# Light_bar.net
KiCad netlist of a schematic drawn in EAGLE
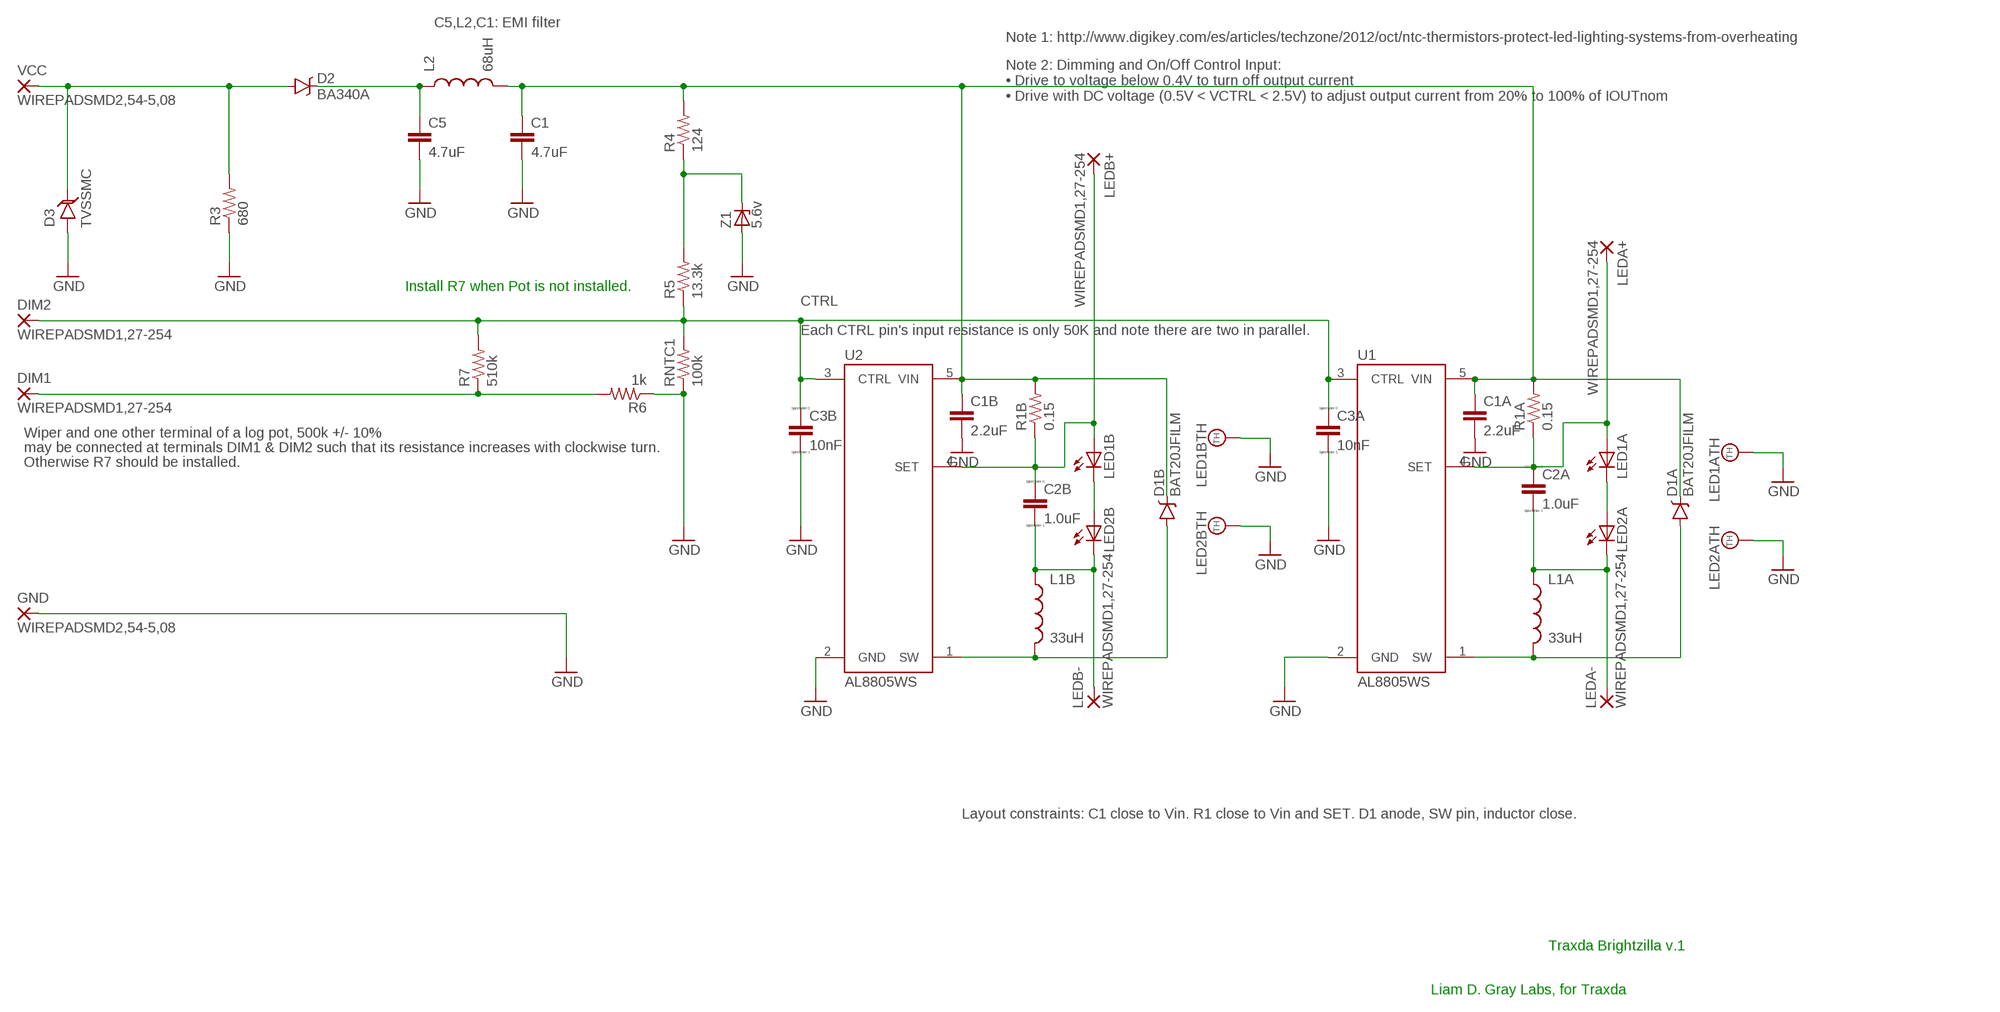
[diagram p0: schematic, sheet 1]

(export (version "E")
  (design (tool "Eeschema 10.0.6"))
  (components
    (comp (ref "C1")
      (value "4.7uF")
      (footprint "eagle-import:1210")
      (libsource (lib "eagle-import") (part "SparkFun-Passives_CAP1210"))
    )
    (comp (ref "C1A")
      (value "2.2uF")
      (footprint "eagle-import:0805")
      (libsource (lib "eagle-import") (part "2.2UF-25V-+80/-20(0805)"))
    )
    (comp (ref "C1B")
      (value "2.2uF")
      (footprint "eagle-import:0805")
      (libsource (lib "eagle-import") (part "2.2UF-25V-+80/-20(0805)"))
    )
    (comp (ref "C2A")
      (value "1.0uF")
      (footprint "eagle-import:0805")
      (libsource (lib "eagle-import") (part "1.0UF-25V-+80/-20(0805)"))
    )
    (comp (ref "C2B")
      (value "1.0uF")
      (footprint "eagle-import:0805")
      (libsource (lib "eagle-import") (part "1.0UF-25V-+80/-20(0805)"))
    )
    (comp (ref "C3A")
      (value "10nF")
      (footprint "eagle-import:0603-CAP")
      (libsource (lib "eagle-import") (part "10NF/10000PF-50V-10%(0603)"))
    )
    (comp (ref "C3B")
      (value "10nF")
      (footprint "eagle-import:0603-CAP")
      (libsource (lib "eagle-import") (part "CAP0603-CAP"))
    )
    (comp (ref "C5")
      (value "4.7uF")
      (footprint "eagle-import:1210")
      (libsource (lib "eagle-import") (part "SparkFun-Passives_CAP1210"))
    )
    (comp (ref "D1A")
      (value "BAT20JFILM")
      (footprint "eagle-import:SOD-323")
      (libsource (lib "eagle-import") (part "BAT20JFILM"))
    )
    (comp (ref "D1B")
      (value "BAT20JFILM")
      (footprint "eagle-import:SOD-323")
      (libsource (lib "eagle-import") (part "BAT20JFILM"))
    )
    (comp (ref "D2")
      (value "BA340A")
      (footprint "eagle-import:SMA-DIODE")
      (libsource (lib "eagle-import") (part "B340A"))
    )
    (comp (ref "D3")
      (value "TVSSMC")
      (footprint "eagle-import:SMC")
      (libsource (lib "eagle-import") (part "TVSSMC"))
    )
    (comp (ref "DIM1")
      (value "WIREPADSMD1,27-254")
      (footprint "eagle-import:SMD1,27-2,54")
      (libsource (lib "eagle-import") (part "WIREPADSMD1,27-254"))
    )
    (comp (ref "DIM2")
      (value "WIREPADSMD1,27-254")
      (footprint "eagle-import:SMD1,27-2,54")
      (libsource (lib "eagle-import") (part "WIREPADSMD1,27-254"))
    )
    (comp (ref "GND")
      (value "WIREPADSMD2,54-5,08")
      (footprint "eagle-import:SMD2,54-5,08")
      (libsource (lib "eagle-import") (part "WIREPADSMD2,54-5,08"))
    )
    (comp (ref "L1A")
      (value "33uH")
      (footprint "eagle-import:NR6045")
      (libsource (lib "eagle-import") (part "INDUCTORYUDEN_NR6045NR6045T330M"))
    )
    (comp (ref "L1B")
      (value "33uH")
      (footprint "eagle-import:NR6045")
      (libsource (lib "eagle-import") (part "INDUCTORYUDEN_NR6045NR6045T330M"))
    )
    (comp (ref "L2")
      (value "68uH")
      (footprint "eagle-import:SRR1260")
      (libsource (lib "eagle-import") (part "INDUCTORBOURNS_SRR1260"))
    )
    (comp (ref "LED1A")
      (value "LUXEON_REBEL")
      (footprint "eagle-import:LUXEON_REBEL_32MIL12MIL")
      (libsource (lib "eagle-import") (part "LUXEON_REBEL"))
    )
    (comp (ref "LED1B")
      (value "LUXEON_REBEL")
      (footprint "eagle-import:LUXEON_REBEL_32MIL12MIL")
      (libsource (lib "eagle-import") (part "LUXEON_REBEL"))
    )
    (comp (ref "LED2A")
      (value "LUXEON_REBEL")
      (footprint "eagle-import:LUXEON_REBEL_32MIL12MIL")
      (libsource (lib "eagle-import") (part "LUXEON_REBEL"))
    )
    (comp (ref "LED2B")
      (value "LUXEON_REBEL")
      (footprint "eagle-import:LUXEON_REBEL_32MIL12MIL")
      (libsource (lib "eagle-import") (part "LUXEON_REBEL"))
    )
    (comp (ref "LEDA+")
      (value "WIREPADSMD1,27-254")
      (footprint "eagle-import:SMD1,27-2,54")
      (libsource (lib "eagle-import") (part "WIREPADSMD1,27-254"))
    )
    (comp (ref "LEDA-")
      (value "WIREPADSMD1,27-254")
      (footprint "eagle-import:SMD1,27-2,54")
      (libsource (lib "eagle-import") (part "WIREPADSMD1,27-254"))
    )
    (comp (ref "LEDB+")
      (value "WIREPADSMD1,27-254")
      (footprint "eagle-import:SMD1,27-2,54")
      (libsource (lib "eagle-import") (part "WIREPADSMD1,27-254"))
    )
    (comp (ref "LEDB-")
      (value "WIREPADSMD1,27-254")
      (footprint "eagle-import:SMD1,27-2,54")
      (libsource (lib "eagle-import") (part "WIREPADSMD1,27-254"))
    )
    (comp (ref "R1A")
      (value "0.15")
      (footprint "eagle-import:0805")
      (libsource (lib "eagle-import") (part "0.3OHM-1/8W-1%(0805)"))
    )
    (comp (ref "R1B")
      (value "0.15")
      (footprint "eagle-import:0805")
      (libsource (lib "eagle-import") (part "0.3OHM-1/8W-1%(0805)"))
    )
    (comp (ref "R3")
      (value "680")
      (footprint "eagle-import:R2512")
      (libsource (lib "eagle-import") (part "RESISTOR2512"))
    )
    (comp (ref "R4")
      (value "124")
      (footprint "eagle-import:R1210")
      (libsource (lib "eagle-import") (part "R-US_R1210"))
    )
    (comp (ref "R5")
      (value "13.3k")
      (footprint "eagle-import:R0805")
      (libsource (lib "eagle-import") (part "R-US_R0805"))
    )
    (comp (ref "R6")
      (value "1k")
      (footprint "eagle-import:0603-RES")
      (libsource (lib "eagle-import") (part "RESISTOR0603-RES"))
    )
    (comp (ref "R7")
      (value "510k")
      (footprint "eagle-import:0805")
      (libsource (lib "eagle-import") (part "RESISTOR0805-RES"))
    )
    (comp (ref "RNTC1")
      (value "100k")
      (footprint "eagle-import:0603-RES")
      (libsource (lib "eagle-import") (part "RESISTOR0603-RES"))
    )
    (comp (ref "U1")
      (value "AL8805WS")
      (footprint "eagle-import:SOT23-5")
      (libsource (lib "eagle-import") (part "AL8805"))
    )
    (comp (ref "U2")
      (value "AL8805WS")
      (footprint "eagle-import:SOT23-5")
      (libsource (lib "eagle-import") (part "AL8805"))
    )
    (comp (ref "VCC")
      (value "WIREPADSMD2,54-5,08")
      (footprint "eagle-import:SMD2,54-5,08")
      (libsource (lib "eagle-import") (part "WIREPADSMD2,54-5,08"))
    )
    (comp (ref "Z1")
      (value "5.6v")
      (footprint "eagle-import:SOD80C")
      (libsource (lib "eagle-import") (part "ZENER-DIODESOD80C"))
    )
  )
  (nets
    (net (code "1") (name "/CTRL") (class "Default")
      (node (ref "C3A") (pin "1") (pinfunction "1_1") (pintype "passive"))
      (node (ref "C3B") (pin "1") (pinfunction "1_1") (pintype "passive"))
      (node (ref "DIM2") (pin "1") (pinfunction "P_1") (pintype "passive"))
      (node (ref "R5") (pin "1") (pinfunction "1_1") (pintype "passive"))
      (node (ref "R7") (pin "2") (pinfunction "2_2") (pintype "passive"))
      (node (ref "RNTC1") (pin "2") (pinfunction "2_2") (pintype "passive"))
      (node (ref "U1") (pin "3") (pinfunction "CTRL_3") (pintype "bidirectional"))
      (node (ref "U2") (pin "3") (pinfunction "CTRL_3") (pintype "bidirectional"))
    )
    (net (code "2") (name "GND") (class "Default")
      (node (ref "C1") (pin "2") (pinfunction "2_2") (pintype "passive"))
      (node (ref "C1A") (pin "2") (pinfunction "2_2") (pintype "passive"))
      (node (ref "C1B") (pin "2") (pinfunction "2_2") (pintype "passive"))
      (node (ref "C3A") (pin "2") (pinfunction "2_2") (pintype "passive"))
      (node (ref "C3B") (pin "2") (pinfunction "2_2") (pintype "passive"))
      (node (ref "C5") (pin "2") (pinfunction "2_2") (pintype "passive"))
      (node (ref "D3") (pin "A") (pinfunction "A_A") (pintype "passive"))
      (node (ref "GND") (pin "1") (pinfunction "P_1") (pintype "passive"))
      (node (ref "LED1A") (pin "TH") (pinfunction "TH_TH") (pintype "passive"))
      (node (ref "LED1A") (pin "TH@1") (pinfunction "TH_TH@1") (pintype "passive"))
      (node (ref "LED1A") (pin "TH@2") (pinfunction "TH_TH@2") (pintype "passive"))
      (node (ref "LED1A") (pin "TH@3") (pinfunction "TH_TH@3") (pintype "passive"))
      (node (ref "LED1A") (pin "TH@4") (pinfunction "TH_TH@4") (pintype "passive"))
      (node (ref "LED1B") (pin "TH") (pinfunction "TH_TH") (pintype "passive"))
      (node (ref "LED1B") (pin "TH@1") (pinfunction "TH_TH@1") (pintype "passive"))
      (node (ref "LED1B") (pin "TH@2") (pinfunction "TH_TH@2") (pintype "passive"))
      (node (ref "LED1B") (pin "TH@3") (pinfunction "TH_TH@3") (pintype "passive"))
      (node (ref "LED1B") (pin "TH@4") (pinfunction "TH_TH@4") (pintype "passive"))
      (node (ref "LED2A") (pin "TH") (pinfunction "TH_TH") (pintype "passive"))
      (node (ref "LED2A") (pin "TH@1") (pinfunction "TH_TH@1") (pintype "passive"))
      (node (ref "LED2A") (pin "TH@2") (pinfunction "TH_TH@2") (pintype "passive"))
      (node (ref "LED2A") (pin "TH@3") (pinfunction "TH_TH@3") (pintype "passive"))
      (node (ref "LED2A") (pin "TH@4") (pinfunction "TH_TH@4") (pintype "passive"))
      (node (ref "LED2B") (pin "TH") (pinfunction "TH_TH") (pintype "passive"))
      (node (ref "LED2B") (pin "TH@1") (pinfunction "TH_TH@1") (pintype "passive"))
      (node (ref "LED2B") (pin "TH@2") (pinfunction "TH_TH@2") (pintype "passive"))
      (node (ref "LED2B") (pin "TH@3") (pinfunction "TH_TH@3") (pintype "passive"))
      (node (ref "LED2B") (pin "TH@4") (pinfunction "TH_TH@4") (pintype "passive"))
      (node (ref "R3") (pin "1") (pinfunction "1_1") (pintype "passive"))
      (node (ref "R6") (pin "1") (pinfunction "1_1") (pintype "passive"))
      (node (ref "RNTC1") (pin "1") (pinfunction "1_1") (pintype "passive"))
      (node (ref "U1") (pin "2") (pinfunction "GND_2") (pintype "bidirectional"))
      (node (ref "U2") (pin "2") (pinfunction "GND_2") (pintype "bidirectional"))
      (node (ref "Z1") (pin "A") (pinfunction "A_A") (pintype "passive"))
    )
    (net (code "3") (name "Net-(C5-Pad1)") (class "Default")
      (node (ref "C5") (pin "1") (pinfunction "1_1") (pintype "passive"))
      (node (ref "D2") (pin "C") (pinfunction "C_C") (pintype "passive"))
      (node (ref "L2") (pin "1") (pinfunction "1_1") (pintype "passive"))
    )
    (net (code "4") (name "Net-(DIM1-P)") (class "Default")
      (node (ref "DIM1") (pin "1") (pinfunction "P_1") (pintype "passive"))
      (node (ref "R6") (pin "2") (pinfunction "2_2") (pintype "passive"))
      (node (ref "R7") (pin "1") (pinfunction "1_1") (pintype "passive"))
    )
    (net (code "5") (name "Net-(LED1A-PadC)") (class "Default")
      (node (ref "LED1A") (pin "C") (pinfunction "C_C") (pintype "passive"))
      (node (ref "LED1A") (pin "C@1") (pinfunction "C_C@1") (pintype "passive"))
      (node (ref "LED2A") (pin "A") (pinfunction "A_A") (pintype "passive"))
      (node (ref "LED2A") (pin "A@1") (pinfunction "A_A@1") (pintype "passive"))
    )
    (net (code "6") (name "Net-(LED1B-PadC)") (class "Default")
      (node (ref "LED1B") (pin "C") (pinfunction "C_C") (pintype "passive"))
      (node (ref "LED1B") (pin "C@1") (pinfunction "C_C@1") (pintype "passive"))
      (node (ref "LED2B") (pin "A") (pinfunction "A_A") (pintype "passive"))
      (node (ref "LED2B") (pin "A@1") (pinfunction "A_A@1") (pintype "passive"))
    )
    (net (code "7") (name "Net-(LEDA+-P)") (class "Default")
      (node (ref "C2A") (pin "1") (pinfunction "1_1") (pintype "passive"))
      (node (ref "LED1A") (pin "A") (pinfunction "A_A") (pintype "passive"))
      (node (ref "LED1A") (pin "A@1") (pinfunction "A_A@1") (pintype "passive"))
      (node (ref "LEDA+") (pin "1") (pinfunction "P_1") (pintype "passive"))
      (node (ref "R1A") (pin "1") (pinfunction "1_1") (pintype "passive"))
      (node (ref "U1") (pin "4") (pinfunction "SET_4") (pintype "bidirectional"))
    )
    (net (code "8") (name "Net-(LEDA--P)") (class "Default")
      (node (ref "C2A") (pin "2") (pinfunction "2_2") (pintype "passive"))
      (node (ref "L1A") (pin "1") (pinfunction "1_1") (pintype "passive"))
      (node (ref "LED2A") (pin "C") (pinfunction "C_C") (pintype "passive"))
      (node (ref "LED2A") (pin "C@1") (pinfunction "C_C@1") (pintype "passive"))
      (node (ref "LEDA-") (pin "1") (pinfunction "P_1") (pintype "passive"))
    )
    (net (code "9") (name "Net-(LEDB+-P)") (class "Default")
      (node (ref "C2B") (pin "1") (pinfunction "1_1") (pintype "passive"))
      (node (ref "LED1B") (pin "A") (pinfunction "A_A") (pintype "passive"))
      (node (ref "LED1B") (pin "A@1") (pinfunction "A_A@1") (pintype "passive"))
      (node (ref "LEDB+") (pin "1") (pinfunction "P_1") (pintype "passive"))
      (node (ref "R1B") (pin "1") (pinfunction "1_1") (pintype "passive"))
      (node (ref "U2") (pin "4") (pinfunction "SET_4") (pintype "bidirectional"))
    )
    (net (code "10") (name "Net-(LEDB--P)") (class "Default")
      (node (ref "C2B") (pin "2") (pinfunction "2_2") (pintype "passive"))
      (node (ref "L1B") (pin "1") (pinfunction "1_1") (pintype "passive"))
      (node (ref "LED2B") (pin "C") (pinfunction "C_C") (pintype "passive"))
      (node (ref "LED2B") (pin "C@1") (pinfunction "C_C@1") (pintype "passive"))
      (node (ref "LEDB-") (pin "1") (pinfunction "P_1") (pintype "passive"))
    )
    (net (code "11") (name "Net-(R4-Pad1)") (class "Default")
      (node (ref "R4") (pin "1") (pinfunction "1_1") (pintype "passive"))
      (node (ref "R5") (pin "2") (pinfunction "2_2") (pintype "passive"))
      (node (ref "Z1") (pin "C") (pinfunction "C_C") (pintype "passive"))
    )
    (net (code "12") (name "Net-(U1-SW)") (class "Default")
      (node (ref "D1A") (pin "A") (pinfunction "A_A") (pintype "passive"))
      (node (ref "L1A") (pin "2") (pinfunction "2_2") (pintype "passive"))
      (node (ref "U1") (pin "1") (pinfunction "SW_1") (pintype "bidirectional"))
    )
    (net (code "13") (name "Net-(U1-VIN)") (class "Default")
      (node (ref "C1") (pin "1") (pinfunction "1_1") (pintype "passive"))
      (node (ref "C1A") (pin "1") (pinfunction "1_1") (pintype "passive"))
      (node (ref "C1B") (pin "1") (pinfunction "1_1") (pintype "passive"))
      (node (ref "D1A") (pin "C") (pinfunction "C_C") (pintype "passive"))
      (node (ref "D1B") (pin "C") (pinfunction "C_C") (pintype "passive"))
      (node (ref "L2") (pin "2") (pinfunction "2_2") (pintype "passive"))
      (node (ref "R1A") (pin "2") (pinfunction "2_2") (pintype "passive"))
      (node (ref "R1B") (pin "2") (pinfunction "2_2") (pintype "passive"))
      (node (ref "R4") (pin "2") (pinfunction "2_2") (pintype "passive"))
      (node (ref "U1") (pin "5") (pinfunction "VIN_5") (pintype "bidirectional"))
      (node (ref "U2") (pin "5") (pinfunction "VIN_5") (pintype "bidirectional"))
    )
    (net (code "14") (name "Net-(U2-SW)") (class "Default")
      (node (ref "D1B") (pin "A") (pinfunction "A_A") (pintype "passive"))
      (node (ref "L1B") (pin "2") (pinfunction "2_2") (pintype "passive"))
      (node (ref "U2") (pin "1") (pinfunction "SW_1") (pintype "bidirectional"))
    )
    (net (code "15") (name "Net-(VCC-P)") (class "Default")
      (node (ref "D2") (pin "A") (pinfunction "A_A") (pintype "passive"))
      (node (ref "D3") (pin "C") (pinfunction "C_C") (pintype "passive"))
      (node (ref "R3") (pin "2") (pinfunction "2_2") (pintype "passive"))
      (node (ref "VCC") (pin "1") (pinfunction "P_1") (pintype "passive"))
    )
  )
)
